# Low-Voltage_Power_Supply.net
KiCad netlist of a schematic drawn in Altium Designer
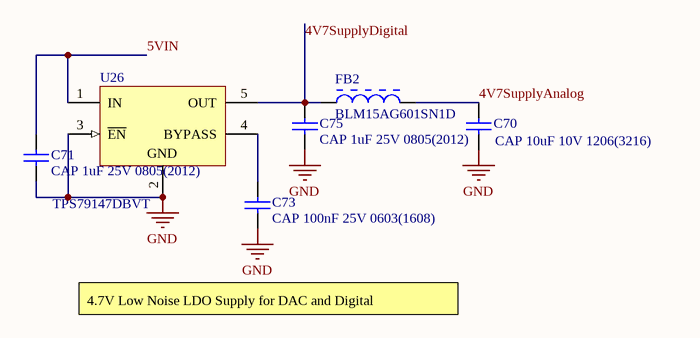
[diagram p0: Low-Voltage Power Supply.SchDoc]

(export (version "E")
  (design (tool "Eeschema 10.0.6"))
  (components
    (comp (ref "C70")
      (value "CAP 10uF 10V 1206(3216)")
      (footprint "CAPC1206(3216)130_L")
      (description "CAP 10uF 10V -20% to +80% 1206 (3216 Metric) Thickness 1.3mm SMD")
      (fields (field (name "TOLERANCE") "-20% to +80%"))
      (libsource (lib "Altium Content Vault") (part "CAP"))
    )
    (comp (ref "C71")
      (value "CAP 1uF 25V 0805(2012)")
      (footprint "CAPC0805(2012)145_N")
      (description "CAP 1uF 25V ±10% 0805 (2012 Metric) Thickness 1.45mm SMD")
      (fields (field (name "TOLERANCE") "Â±10%"))
      (libsource (lib "Altium Content Vault") (part "CAP"))
    )
    (comp (ref "C73")
      (value "CAP 100nF 25V 0603(1608)")
      (footprint "CAPC0603(1608)100_N")
      (description "CAP 100nF 25V ±20% 0603 (1608 Metric) Thickness 1mm SMD")
      (fields (field (name "TOLERANCE") "Â±20%"))
      (libsource (lib "Altium Content Vault") (part "CAP"))
    )
    (comp (ref "C75")
      (value "CAP 1uF 25V 0805(2012)")
      (footprint "CAPC0805(2012)145_N")
      (description "CAP 1uF 25V ±10% 0805 (2012 Metric) Thickness 1.45mm SMD")
      (fields (field (name "TOLERANCE") "Â±10%"))
      (libsource (lib "Altium Content Vault") (part "CAP"))
    )
    (comp (ref "FB2")
      (value "BLM15AG601SN1D")
      (footprint "MURA-BLM15-CHIP-2_V")
      (fields (field (name "MANUFACTURER") "Murata"))
      (libsource (lib "Altium Content Vault") (part "MURA-FB-2"))
    )
    (comp (ref "U26")
      (value "TPS79147DBVT")
      (footprint "TI-DBV5_N")
      (fields (field (name "MANUFACTURER") "Texas Instruments"))
      (libsource (lib "Altium Content Vault") (part "TI-TPS7XXXX-DBV5_A"))
    )
  )
  (nets
    (net (code "1") (name "/4V7SupplyAnalog") (class "Default")
      (node (ref "C70") (pin "2") (pinfunction "2_2") (pintype "passive"))
      (node (ref "FB2") (pin "2") (pinfunction "2_2") (pintype "passive"))
    )
    (net (code "2") (name "/4V7SupplyDigital") (class "Default")
      (node (ref "C75") (pin "1") (pinfunction "1_1") (pintype "passive"))
      (node (ref "FB2") (pin "1") (pinfunction "1_1") (pintype "passive"))
      (node (ref "U26") (pin "5") (pinfunction "OUT_5") (pintype "power_in"))
    )
    (net (code "3") (name "/5VIN") (class "Default")
      (node (ref "C71") (pin "2") (pinfunction "2_2") (pintype "passive"))
      (node (ref "U26") (pin "1") (pinfunction "IN_1") (pintype "power_in"))
    )
    (net (code "4") (name "GND") (class "Default")
      (node (ref "C70") (pin "1") (pinfunction "1_1") (pintype "passive"))
      (node (ref "C71") (pin "1") (pinfunction "1_1") (pintype "passive"))
      (node (ref "C73") (pin "2") (pinfunction "2_2") (pintype "passive"))
      (node (ref "C75") (pin "2") (pinfunction "2_2") (pintype "passive"))
      (node (ref "U26") (pin "2") (pinfunction "GND_2") (pintype "power_in"))
      (node (ref "U26") (pin "3") (pinfunction "~{EN}_3") (pintype "input"))
    )
    (net (code "5") (name "Net-(U26-BYPASS)") (class "Default")
      (node (ref "C73") (pin "1") (pinfunction "1_1") (pintype "passive"))
      (node (ref "U26") (pin "4") (pinfunction "BYPASS_4") (pintype "passive"))
    )
  )
)
